# M3_Chip.net
KiCad netlist of a schematic drawn in Altium Designer
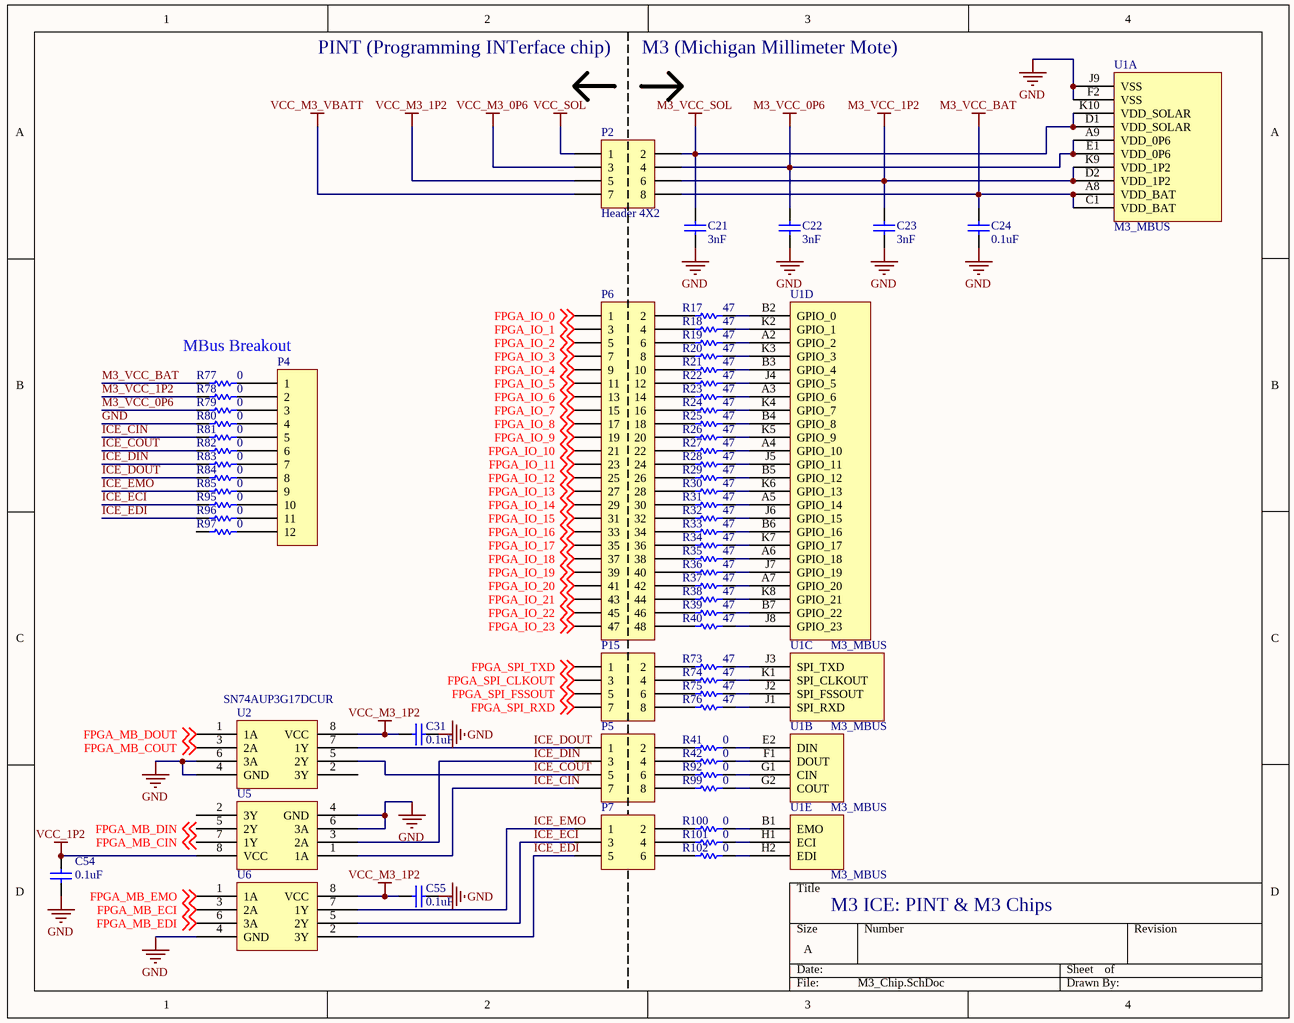
[diagram p0: M3_Chip.SchDoc]

(export (version "E")
  (design (tool "Eeschema 10.0.6"))
  (components
    (comp (ref "C21")
      (value "3nF")
      (footprint "1608[0603]")
      (description "Capacitor (Semiconductor SIM Model)")
      (fields
        (field (name "DISTPARTNO") "399-7893-1-ND")
        (field (name "MANPARTNO") "C0603C302K5GACTU")
        (field (name "PUBLISHER") "Altium Limited")
      )
      (libsource (lib "Miscellaneous Devices") (part "Cap Semi"))
    )
    (comp (ref "C22")
      (value "3nF")
      (footprint "1608[0603]")
      (description "Capacitor (Semiconductor SIM Model)")
      (fields
        (field (name "DISTPARTNO") "399-7893-1-ND")
        (field (name "MANPARTNO") "C0603C302K5GACTU")
        (field (name "PUBLISHER") "Altium Limited")
      )
      (libsource (lib "Miscellaneous Devices") (part "Cap Semi"))
    )
    (comp (ref "C23")
      (value "3nF")
      (footprint "1608[0603]")
      (description "Capacitor (Semiconductor SIM Model)")
      (fields
        (field (name "DISTPARTNO") "399-7893-1-ND")
        (field (name "MANPARTNO") "C0603C302K5GACTU")
        (field (name "PUBLISHER") "Altium Limited")
      )
      (libsource (lib "Miscellaneous Devices") (part "Cap Semi"))
    )
    (comp (ref "C24")
      (value "0.1uF")
      (footprint "1608[0603]")
      (description "Capacitor (Semiconductor SIM Model)")
      (fields
        (field (name "DISTPARTNO") "445-1317-1-ND")
        (field (name "MANPARTNO") "C1608X7R1C104K")
        (field (name "PUBLISHER") "Altium Limited")
      )
      (libsource (lib "Miscellaneous Devices") (part "Cap Semi"))
    )
    (comp (ref "C31")
      (value "0.1uF")
      (footprint "1608[0603]")
      (description "Capacitor (Semiconductor SIM Model)")
      (fields
        (field (name "DISTPARTNO") "445-1317-1-ND")
        (field (name "MANPARTNO") "C1608X7R1C104K")
        (field (name "PUBLISHER") "Altium Limited")
      )
      (libsource (lib "Miscellaneous Devices") (part "Cap Semi"))
    )
    (comp (ref "C54")
      (value "0.1uF")
      (footprint "1608[0603]")
      (description "Capacitor (Semiconductor SIM Model)")
      (fields
        (field (name "DISTPARTNO") "445-1317-1-ND")
        (field (name "MANPARTNO") "C1608X7R1C104K")
        (field (name "PUBLISHER") "Altium Limited")
      )
      (libsource (lib "Miscellaneous Devices") (part "Cap Semi"))
    )
    (comp (ref "C55")
      (value "0.1uF")
      (footprint "1608[0603]")
      (description "Capacitor (Semiconductor SIM Model)")
      (fields
        (field (name "DISTPARTNO") "445-1317-1-ND")
        (field (name "MANPARTNO") "C1608X7R1C104K")
        (field (name "PUBLISHER") "Altium Limited")
      )
      (libsource (lib "Miscellaneous Devices") (part "Cap Semi"))
    )
    (comp (ref "P2")
      (value "Header 4X2")
      (footprint "HDR2X4")
      (description "Header, 4-Pin, Dual row")
      (fields (field (name "PUBLISHER") "Altium Limited"))
      (libsource (lib "Miscellaneous Connectors") (part "Header 4X2"))
    )
    (comp (ref "P4")
      (value "MBus Breakout")
      (footprint "HDR1X12")
      (description "Header, 12-Pin")
      (fields (field (name "PUBLISHER") "Altium Limited"))
      (libsource (lib "Miscellaneous Connectors") (part "Header 12"))
    )
    (comp (ref "P5")
      (value "Header 4X2")
      (footprint "HDR2X4")
      (description "Header, 4-Pin, Dual row")
      (fields (field (name "PUBLISHER") "Altium Limited"))
      (libsource (lib "Miscellaneous Connectors") (part "Header 4X2"))
    )
    (comp (ref "P6")
      (value "Header 24X2")
      (footprint "HDR2X24")
      (description "Header, 24-Pin, Dual row")
      (fields (field (name "MANPARTNO") "4-103328-0") (field (name "PUBLISHER") "Altium Limited"))
      (libsource (lib "Miscellaneous Connectors") (part "Header 24X2"))
    )
    (comp (ref "P7")
      (value "Header 3X2")
      (footprint "HDR2X3")
      (description "Header, 3-Pin, Dual row")
      (fields (field (name "PUBLISHER") "Altium Limited"))
      (libsource (lib "Miscellaneous Connectors") (part "Header 3X2"))
    )
    (comp (ref "P15")
      (value "Header 4X2")
      (footprint "HDR2X4")
      (description "Header, 4-Pin, Dual row")
      (fields (field (name "PUBLISHER") "Altium Limited"))
      (libsource (lib "Miscellaneous Connectors") (part "Header 4X2"))
    )
    (comp (ref "R17")
      (value "47")
      (footprint "0603")
      (description "Semiconductor Resistor")
      (fields
        (field (name "DISTPARTNO") "P47GCT-ND")
        (field (name "MANPARTNO") "ERJ-3GEYJ470V")
        (field (name "PUBLISHER") "Altium Limited")
      )
      (libsource (lib "M3") (part "Res Chip"))
    )
    (comp (ref "R18")
      (value "47")
      (footprint "0603")
      (description "Semiconductor Resistor")
      (fields
        (field (name "DISTPARTNO") "P47GCT-ND")
        (field (name "MANPARTNO") "ERJ-3GEYJ470V")
        (field (name "PUBLISHER") "Altium Limited")
      )
      (libsource (lib "M3") (part "Res Chip"))
    )
    (comp (ref "R19")
      (value "47")
      (footprint "0603")
      (description "Semiconductor Resistor")
      (fields
        (field (name "DISTPARTNO") "P47GCT-ND")
        (field (name "MANPARTNO") "ERJ-3GEYJ470V")
        (field (name "PUBLISHER") "Altium Limited")
      )
      (libsource (lib "M3") (part "Res Chip"))
    )
    (comp (ref "R20")
      (value "47")
      (footprint "0603")
      (description "Semiconductor Resistor")
      (fields
        (field (name "DISTPARTNO") "P47GCT-ND")
        (field (name "MANPARTNO") "ERJ-3GEYJ470V")
        (field (name "PUBLISHER") "Altium Limited")
      )
      (libsource (lib "M3") (part "Res Chip"))
    )
    (comp (ref "R21")
      (value "47")
      (footprint "0603")
      (description "Semiconductor Resistor")
      (fields
        (field (name "DISTPARTNO") "P47GCT-ND")
        (field (name "MANPARTNO") "ERJ-3GEYJ470V")
        (field (name "PUBLISHER") "Altium Limited")
      )
      (libsource (lib "M3") (part "Res Chip"))
    )
    (comp (ref "R22")
      (value "47")
      (footprint "0603")
      (description "Semiconductor Resistor")
      (fields
        (field (name "DISTPARTNO") "P47GCT-ND")
        (field (name "MANPARTNO") "ERJ-3GEYJ470V")
        (field (name "PUBLISHER") "Altium Limited")
      )
      (libsource (lib "M3") (part "Res Chip"))
    )
    (comp (ref "R23")
      (value "47")
      (footprint "0603")
      (description "Semiconductor Resistor")
      (fields
        (field (name "DISTPARTNO") "P47GCT-ND")
        (field (name "MANPARTNO") "ERJ-3GEYJ470V")
        (field (name "PUBLISHER") "Altium Limited")
      )
      (libsource (lib "M3") (part "Res Chip"))
    )
    (comp (ref "R24")
      (value "47")
      (footprint "0603")
      (description "Semiconductor Resistor")
      (fields
        (field (name "DISTPARTNO") "P47GCT-ND")
        (field (name "MANPARTNO") "ERJ-3GEYJ470V")
        (field (name "PUBLISHER") "Altium Limited")
      )
      (libsource (lib "M3") (part "Res Chip"))
    )
    (comp (ref "R25")
      (value "47")
      (footprint "0603")
      (description "Semiconductor Resistor")
      (fields
        (field (name "DISTPARTNO") "P47GCT-ND")
        (field (name "MANPARTNO") "ERJ-3GEYJ470V")
        (field (name "PUBLISHER") "Altium Limited")
      )
      (libsource (lib "M3") (part "Res Chip"))
    )
    (comp (ref "R26")
      (value "47")
      (footprint "0603")
      (description "Semiconductor Resistor")
      (fields
        (field (name "DISTPARTNO") "P47GCT-ND")
        (field (name "MANPARTNO") "ERJ-3GEYJ470V")
        (field (name "PUBLISHER") "Altium Limited")
      )
      (libsource (lib "M3") (part "Res Chip"))
    )
    (comp (ref "R27")
      (value "47")
      (footprint "0603")
      (description "Semiconductor Resistor")
      (fields
        (field (name "DISTPARTNO") "P47GCT-ND")
        (field (name "MANPARTNO") "ERJ-3GEYJ470V")
        (field (name "PUBLISHER") "Altium Limited")
      )
      (libsource (lib "M3") (part "Res Chip"))
    )
    (comp (ref "R28")
      (value "47")
      (footprint "0603")
      (description "Semiconductor Resistor")
      (fields
        (field (name "DISTPARTNO") "P47GCT-ND")
        (field (name "MANPARTNO") "ERJ-3GEYJ470V")
        (field (name "PUBLISHER") "Altium Limited")
      )
      (libsource (lib "M3") (part "Res Chip"))
    )
    (comp (ref "R29")
      (value "47")
      (footprint "0603")
      (description "Semiconductor Resistor")
      (fields
        (field (name "DISTPARTNO") "P47GCT-ND")
        (field (name "MANPARTNO") "ERJ-3GEYJ470V")
        (field (name "PUBLISHER") "Altium Limited")
      )
      (libsource (lib "M3") (part "Res Chip"))
    )
    (comp (ref "R30")
      (value "47")
      (footprint "0603")
      (description "Semiconductor Resistor")
      (fields
        (field (name "DISTPARTNO") "P47GCT-ND")
        (field (name "MANPARTNO") "ERJ-3GEYJ470V")
        (field (name "PUBLISHER") "Altium Limited")
      )
      (libsource (lib "M3") (part "Res Chip"))
    )
    (comp (ref "R31")
      (value "47")
      (footprint "0603")
      (description "Semiconductor Resistor")
      (fields
        (field (name "DISTPARTNO") "P47GCT-ND")
        (field (name "MANPARTNO") "ERJ-3GEYJ470V")
        (field (name "PUBLISHER") "Altium Limited")
      )
      (libsource (lib "M3") (part "Res Chip"))
    )
    (comp (ref "R32")
      (value "47")
      (footprint "0603")
      (description "Semiconductor Resistor")
      (fields
        (field (name "DISTPARTNO") "P47GCT-ND")
        (field (name "MANPARTNO") "ERJ-3GEYJ470V")
        (field (name "PUBLISHER") "Altium Limited")
      )
      (libsource (lib "M3") (part "Res Chip"))
    )
    (comp (ref "R33")
      (value "47")
      (footprint "0603")
      (description "Semiconductor Resistor")
      (fields
        (field (name "DISTPARTNO") "P47GCT-ND")
        (field (name "MANPARTNO") "ERJ-3GEYJ470V")
        (field (name "PUBLISHER") "Altium Limited")
      )
      (libsource (lib "M3") (part "Res Chip"))
    )
    (comp (ref "R34")
      (value "47")
      (footprint "0603")
      (description "Semiconductor Resistor")
      (fields
        (field (name "DISTPARTNO") "P47GCT-ND")
        (field (name "MANPARTNO") "ERJ-3GEYJ470V")
        (field (name "PUBLISHER") "Altium Limited")
      )
      (libsource (lib "M3") (part "Res Chip"))
    )
    (comp (ref "R35")
      (value "47")
      (footprint "0603")
      (description "Semiconductor Resistor")
      (fields
        (field (name "DISTPARTNO") "P47GCT-ND")
        (field (name "MANPARTNO") "ERJ-3GEYJ470V")
        (field (name "PUBLISHER") "Altium Limited")
      )
      (libsource (lib "M3") (part "Res Chip"))
    )
    (comp (ref "R36")
      (value "47")
      (footprint "0603")
      (description "Semiconductor Resistor")
      (fields
        (field (name "DISTPARTNO") "P47GCT-ND")
        (field (name "MANPARTNO") "ERJ-3GEYJ470V")
        (field (name "PUBLISHER") "Altium Limited")
      )
      (libsource (lib "M3") (part "Res Chip"))
    )
    (comp (ref "R37")
      (value "47")
      (footprint "0603")
      (description "Semiconductor Resistor")
      (fields
        (field (name "DISTPARTNO") "P47GCT-ND")
        (field (name "MANPARTNO") "ERJ-3GEYJ470V")
        (field (name "PUBLISHER") "Altium Limited")
      )
      (libsource (lib "M3") (part "Res Chip"))
    )
    (comp (ref "R38")
      (value "47")
      (footprint "0603")
      (description "Semiconductor Resistor")
      (fields
        (field (name "DISTPARTNO") "P47GCT-ND")
        (field (name "MANPARTNO") "ERJ-3GEYJ470V")
        (field (name "PUBLISHER") "Altium Limited")
      )
      (libsource (lib "M3") (part "Res Chip"))
    )
    (comp (ref "R39")
      (value "47")
      (footprint "0603")
      (description "Semiconductor Resistor")
      (fields
        (field (name "DISTPARTNO") "P47GCT-ND")
        (field (name "MANPARTNO") "ERJ-3GEYJ470V")
        (field (name "PUBLISHER") "Altium Limited")
      )
      (libsource (lib "M3") (part "Res Chip"))
    )
    (comp (ref "R40")
      (value "47")
      (footprint "0603")
      (description "Semiconductor Resistor")
      (fields
        (field (name "DISTPARTNO") "P47GCT-ND")
        (field (name "MANPARTNO") "ERJ-3GEYJ470V")
        (field (name "PUBLISHER") "Altium Limited")
      )
      (libsource (lib "M3") (part "Res Chip"))
    )
    (comp (ref "R41")
      (value "0")
      (footprint "0603")
      (description "Semiconductor Resistor")
      (fields
        (field (name "DISTPARTNO") "P0.0GCT-ND")
        (field (name "MANPARTNO") "ERJ-3GEY0R00V")
        (field (name "PUBLISHER") "Altium Limited")
      )
      (libsource (lib "M3") (part "Res Chip"))
    )
    (comp (ref "R42")
      (value "0")
      (footprint "0603")
      (description "Semiconductor Resistor")
      (fields
        (field (name "DISTPARTNO") "P0.0GCT-ND")
        (field (name "MANPARTNO") "ERJ-3GEY0R00V")
        (field (name "PUBLISHER") "Altium Limited")
      )
      (libsource (lib "M3") (part "Res Chip"))
    )
    (comp (ref "R73")
      (value "47")
      (footprint "0603")
      (description "Semiconductor Resistor")
      (fields
        (field (name "DISTPARTNO") "P47GCT-ND")
        (field (name "MANPARTNO") "ERJ-3GEYJ470V")
        (field (name "PUBLISHER") "Altium Limited")
      )
      (libsource (lib "M3") (part "Res Chip"))
    )
    (comp (ref "R74")
      (value "47")
      (footprint "0603")
      (description "Semiconductor Resistor")
      (fields
        (field (name "DISTPARTNO") "P47GCT-ND")
        (field (name "MANPARTNO") "ERJ-3GEYJ470V")
        (field (name "PUBLISHER") "Altium Limited")
      )
      (libsource (lib "M3") (part "Res Chip"))
    )
    (comp (ref "R75")
      (value "47")
      (footprint "0603")
      (description "Semiconductor Resistor")
      (fields
        (field (name "DISTPARTNO") "P47GCT-ND")
        (field (name "MANPARTNO") "ERJ-3GEYJ470V")
        (field (name "PUBLISHER") "Altium Limited")
      )
      (libsource (lib "M3") (part "Res Chip"))
    )
    (comp (ref "R76")
      (value "47")
      (footprint "0603")
      (description "Semiconductor Resistor")
      (fields
        (field (name "DISTPARTNO") "P47GCT-ND")
        (field (name "MANPARTNO") "ERJ-3GEYJ470V")
        (field (name "PUBLISHER") "Altium Limited")
      )
      (libsource (lib "M3") (part "Res Chip"))
    )
    (comp (ref "R77")
      (value "0")
      (footprint "0603")
      (description "Semiconductor Resistor")
      (fields
        (field (name "DISTPARTNO") "P0.0GCT-ND")
        (field (name "MANPARTNO") "ERJ-3GEY0R00V")
        (field (name "PUBLISHER") "Altium Limited")
      )
      (libsource (lib "M3") (part "Res Chip"))
    )
    (comp (ref "R78")
      (value "0")
      (footprint "0603")
      (description "Semiconductor Resistor")
      (fields
        (field (name "DISTPARTNO") "P0.0GCT-ND")
        (field (name "MANPARTNO") "ERJ-3GEY0R00V")
        (field (name "PUBLISHER") "Altium Limited")
      )
      (libsource (lib "M3") (part "Res Chip"))
    )
    (comp (ref "R79")
      (value "0")
      (footprint "0603")
      (description "Semiconductor Resistor")
      (fields
        (field (name "DISTPARTNO") "P0.0GCT-ND")
        (field (name "MANPARTNO") "ERJ-3GEY0R00V")
        (field (name "PUBLISHER") "Altium Limited")
      )
      (libsource (lib "M3") (part "Res Chip"))
    )
    (comp (ref "R80")
      (value "0")
      (footprint "0603")
      (description "Semiconductor Resistor")
      (fields
        (field (name "DISTPARTNO") "P0.0GCT-ND")
        (field (name "MANPARTNO") "ERJ-3GEY0R00V")
        (field (name "PUBLISHER") "Altium Limited")
      )
      (libsource (lib "M3") (part "Res Chip"))
    )
    (comp (ref "R81")
      (value "0")
      (footprint "0603")
      (description "Semiconductor Resistor")
      (fields
        (field (name "DISTPARTNO") "P0.0GCT-ND")
        (field (name "MANPARTNO") "ERJ-3GEY0R00V")
        (field (name "PUBLISHER") "Altium Limited")
      )
      (libsource (lib "M3") (part "Res Chip"))
    )
    (comp (ref "R82")
      (value "0")
      (footprint "0603")
      (description "Semiconductor Resistor")
      (fields
        (field (name "DISTPARTNO") "P0.0GCT-ND")
        (field (name "MANPARTNO") "ERJ-3GEY0R00V")
        (field (name "PUBLISHER") "Altium Limited")
      )
      (libsource (lib "M3") (part "Res Chip"))
    )
    (comp (ref "R83")
      (value "0")
      (footprint "0603")
      (description "Semiconductor Resistor")
      (fields
        (field (name "DISTPARTNO") "P0.0GCT-ND")
        (field (name "MANPARTNO") "ERJ-3GEY0R00V")
        (field (name "PUBLISHER") "Altium Limited")
      )
      (libsource (lib "M3") (part "Res Chip"))
    )
    (comp (ref "R84")
      (value "0")
      (footprint "0603")
      (description "Semiconductor Resistor")
      (fields
        (field (name "DISTPARTNO") "P0.0GCT-ND")
        (field (name "MANPARTNO") "ERJ-3GEY0R00V")
        (field (name "PUBLISHER") "Altium Limited")
      )
      (libsource (lib "M3") (part "Res Chip"))
    )
    (comp (ref "R85")
      (value "0")
      (footprint "0603")
      (description "Semiconductor Resistor")
      (fields
        (field (name "DISTPARTNO") "P0.0GCT-ND")
        (field (name "MANPARTNO") "ERJ-3GEY0R00V")
        (field (name "PUBLISHER") "Altium Limited")
      )
      (libsource (lib "M3") (part "Res Chip"))
    )
    (comp (ref "R92")
      (value "0")
      (footprint "0603")
      (description "Semiconductor Resistor")
      (fields
        (field (name "DISTPARTNO") "P0.0GCT-ND")
        (field (name "MANPARTNO") "ERJ-3GEY0R00V")
        (field (name "PUBLISHER") "Altium Limited")
      )
      (libsource (lib "M3") (part "Res Chip"))
    )
    (comp (ref "R95")
      (value "0")
      (footprint "0603")
      (description "Semiconductor Resistor")
      (fields
        (field (name "DISTPARTNO") "P0.0GCT-ND")
        (field (name "MANPARTNO") "ERJ-3GEY0R00V")
        (field (name "PUBLISHER") "Altium Limited")
      )
      (libsource (lib "M3") (part "Res Chip"))
    )
    (comp (ref "R96")
      (value "0")
      (footprint "0603")
      (description "Semiconductor Resistor")
      (fields
        (field (name "DISTPARTNO") "P0.0GCT-ND")
        (field (name "MANPARTNO") "ERJ-3GEY0R00V")
        (field (name "PUBLISHER") "Altium Limited")
      )
      (libsource (lib "M3") (part "Res Chip"))
    )
    (comp (ref "R97")
      (value "0")
      (footprint "0603")
      (description "Semiconductor Resistor")
      (fields
        (field (name "DISTPARTNO") "P0.0GCT-ND")
        (field (name "MANPARTNO") "ERJ-3GEY0R00V")
        (field (name "PUBLISHER") "Altium Limited")
      )
      (libsource (lib "M3") (part "Res Chip"))
    )
    (comp (ref "R99")
      (value "0")
      (footprint "0603")
      (description "Semiconductor Resistor")
      (fields
        (field (name "DISTPARTNO") "P0.0GCT-ND")
        (field (name "MANPARTNO") "ERJ-3GEY0R00V")
        (field (name "PUBLISHER") "Altium Limited")
      )
      (libsource (lib "M3") (part "Res Chip"))
    )
    (comp (ref "R100")
      (value "0")
      (footprint "0603")
      (description "Semiconductor Resistor")
      (fields
        (field (name "DISTPARTNO") "P0.0GCT-ND")
        (field (name "MANPARTNO") "ERJ-3GEY0R00V")
        (field (name "PUBLISHER") "Altium Limited")
      )
      (libsource (lib "M3") (part "Res Chip"))
    )
    (comp (ref "R101")
      (value "0")
      (footprint "0603")
      (description "Semiconductor Resistor")
      (fields
        (field (name "DISTPARTNO") "P0.0GCT-ND")
        (field (name "MANPARTNO") "ERJ-3GEY0R00V")
        (field (name "PUBLISHER") "Altium Limited")
      )
      (libsource (lib "M3") (part "Res Chip"))
    )
    (comp (ref "R102")
      (value "0")
      (footprint "0603")
      (description "Semiconductor Resistor")
      (fields
        (field (name "DISTPARTNO") "P0.0GCT-ND")
        (field (name "MANPARTNO") "ERJ-3GEY0R00V")
        (field (name "PUBLISHER") "Altium Limited")
      )
      (libsource (lib "M3") (part "Res Chip"))
    )
    (comp (ref "U1")
      (value "M3_MBUS")
      (footprint "CPGA-65")
      (fields (field (name "DISTPARTNO") "3M5067-ND") (field (name "MANPARTNO") "200-6311-9UN-1900"))
      (libsource (lib "M3") (part "M3_MBUS"))
    )
    (comp (ref "U2")
      (value "SN74AUP3G17DCUR")
      (footprint "VFSOP-8")
      (fields (field (name "DISTPARTNO") "296-25596-1-ND"))
      (libsource (lib "") (part "SN74AUP3G17DCUR_1"))
    )
    (comp (ref "U5")
      (value "SN74AUP3G17DCUR")
      (footprint "VFSOP-8")
      (fields (field (name "DISTPARTNO") "296-25596-1-ND"))
      (libsource (lib "M3") (part "SN74AUP3G17DCUR"))
    )
    (comp (ref "U6")
      (value "SN74AUP3G17DCUR")
      (footprint "VFSOP-8")
      (fields (field (name "DISTPARTNO") "296-25596-1-ND"))
      (libsource (lib "") (part "SN74AUP3G17DCUR_1"))
    )
  )
  (nets
    (net (code "1") (name "/ICE_CIN") (class "Default")
      (node (ref "P5") (pin "7") (pinfunction "7_7") (pintype "passive"))
      (node (ref "R81") (pin "2") (pinfunction "2_2") (pintype "passive"))
      (node (ref "U5") (pin "1") (pinfunction "1A_1") (pintype "passive"))
    )
    (net (code "2") (name "/ICE_COUT") (class "Default")
      (node (ref "P5") (pin "5") (pinfunction "5_5") (pintype "passive"))
      (node (ref "R82") (pin "2") (pinfunction "2_2") (pintype "passive"))
      (node (ref "U2") (pin "5") (pinfunction "2Y_5") (pintype "passive"))
    )
    (net (code "3") (name "/ICE_DIN") (class "Default")
      (node (ref "P5") (pin "3") (pinfunction "3_3") (pintype "passive"))
      (node (ref "R83") (pin "2") (pinfunction "2_2") (pintype "passive"))
      (node (ref "U5") (pin "3") (pinfunction "2A_3") (pintype "passive"))
    )
    (net (code "4") (name "/ICE_DOUT") (class "Default")
      (node (ref "P5") (pin "1") (pinfunction "1_1") (pintype "passive"))
      (node (ref "R84") (pin "2") (pinfunction "2_2") (pintype "passive"))
      (node (ref "U2") (pin "7") (pinfunction "1Y_7") (pintype "passive"))
    )
    (net (code "5") (name "/ICE_ECI") (class "Default")
      (node (ref "P7") (pin "3") (pinfunction "3_3") (pintype "passive"))
      (node (ref "R95") (pin "2") (pinfunction "2_2") (pintype "passive"))
      (node (ref "U6") (pin "5") (pinfunction "2Y_5") (pintype "passive"))
    )
    (net (code "6") (name "/ICE_EDI") (class "Default")
      (node (ref "P7") (pin "5") (pinfunction "5_5") (pintype "passive"))
      (node (ref "R96") (pin "2") (pinfunction "2_2") (pintype "passive"))
      (node (ref "U6") (pin "2") (pinfunction "3Y_2") (pintype "passive"))
    )
    (net (code "7") (name "/ICE_EMO") (class "Default")
      (node (ref "P7") (pin "1") (pinfunction "1_1") (pintype "passive"))
      (node (ref "R85") (pin "2") (pinfunction "2_2") (pintype "passive"))
      (node (ref "U6") (pin "7") (pinfunction "1Y_7") (pintype "passive"))
    )
    (net (code "8") (name "FPGA_IO_0") (class "Default")
      (node (ref "P6") (pin "1") (pinfunction "1_1") (pintype "passive"))
    )
    (net (code "9") (name "FPGA_IO_1") (class "Default")
      (node (ref "P6") (pin "3") (pinfunction "3_3") (pintype "passive"))
    )
    (net (code "10") (name "FPGA_IO_2") (class "Default")
      (node (ref "P6") (pin "5") (pinfunction "5_5") (pintype "passive"))
    )
    (net (code "11") (name "FPGA_IO_3") (class "Default")
      (node (ref "P6") (pin "7") (pinfunction "7_7") (pintype "passive"))
    )
    (net (code "12") (name "FPGA_IO_4") (class "Default")
      (node (ref "P6") (pin "9") (pinfunction "9_9") (pintype "passive"))
    )
    (net (code "13") (name "FPGA_IO_5") (class "Default")
      (node (ref "P6") (pin "11") (pinfunction "11_11") (pintype "passive"))
    )
    (net (code "14") (name "FPGA_IO_6") (class "Default")
      (node (ref "P6") (pin "13") (pinfunction "13_13") (pintype "passive"))
    )
    (net (code "15") (name "FPGA_IO_7") (class "Default")
      (node (ref "P6") (pin "15") (pinfunction "15_15") (pintype "passive"))
    )
    (net (code "16") (name "FPGA_IO_8") (class "Default")
      (node (ref "P6") (pin "17") (pinfunction "17_17") (pintype "passive"))
    )
    (net (code "17") (name "FPGA_IO_9") (class "Default")
      (node (ref "P6") (pin "19") (pinfunction "19_19") (pintype "passive"))
    )
    (net (code "18") (name "FPGA_IO_10") (class "Default")
      (node (ref "P6") (pin "21") (pinfunction "21_21") (pintype "passive"))
    )
    (net (code "19") (name "FPGA_IO_11") (class "Default")
      (node (ref "P6") (pin "23") (pinfunction "23_23") (pintype "passive"))
    )
    (net (code "20") (name "FPGA_IO_12") (class "Default")
      (node (ref "P6") (pin "25") (pinfunction "25_25") (pintype "passive"))
    )
    (net (code "21") (name "FPGA_IO_13") (class "Default")
      (node (ref "P6") (pin "27") (pinfunction "27_27") (pintype "passive"))
    )
    (net (code "22") (name "FPGA_IO_14") (class "Default")
      (node (ref "P6") (pin "29") (pinfunction "29_29") (pintype "passive"))
    )
    (net (code "23") (name "FPGA_IO_15") (class "Default")
      (node (ref "P6") (pin "31") (pinfunction "31_31") (pintype "passive"))
    )
    (net (code "24") (name "FPGA_IO_16") (class "Default")
      (node (ref "P6") (pin "33") (pinfunction "33_33") (pintype "passive"))
    )
    (net (code "25") (name "FPGA_IO_17") (class "Default")
      (node (ref "P6") (pin "35") (pinfunction "35_35") (pintype "passive"))
    )
    (net (code "26") (name "FPGA_IO_18") (class "Default")
      (node (ref "P6") (pin "37") (pinfunction "37_37") (pintype "passive"))
    )
    (net (code "27") (name "FPGA_IO_19") (class "Default")
      (node (ref "P6") (pin "39") (pinfunction "39_39") (pintype "passive"))
    )
    (net (code "28") (name "FPGA_IO_20") (class "Default")
      (node (ref "P6") (pin "41") (pinfunction "41_41") (pintype "passive"))
    )
    (net (code "29") (name "FPGA_IO_21") (class "Default")
      (node (ref "P6") (pin "43") (pinfunction "43_43") (pintype "passive"))
    )
    (net (code "30") (name "FPGA_IO_22") (class "Default")
      (node (ref "P6") (pin "45") (pinfunction "45_45") (pintype "passive"))
    )
    (net (code "31") (name "FPGA_IO_23") (class "Default")
      (node (ref "P6") (pin "47") (pinfunction "47_47") (pintype "passive"))
    )
    (net (code "32") (name "FPGA_MB_CIN") (class "Default")
      (node (ref "U5") (pin "7") (pinfunction "1Y_7") (pintype "passive"))
    )
    (net (code "33") (name "FPGA_MB_COUT") (class "Default")
      (node (ref "U2") (pin "3") (pinfunction "2A_3") (pintype "passive"))
    )
    (net (code "34") (name "FPGA_MB_DIN") (class "Default")
      (node (ref "U5") (pin "5") (pinfunction "2Y_5") (pintype "passive"))
    )
    (net (code "35") (name "FPGA_MB_DOUT") (class "Default")
      (node (ref "U2") (pin "1") (pinfunction "1A_1") (pintype "passive"))
    )
    (net (code "36") (name "FPGA_MB_ECI") (class "Default")
      (node (ref "U6") (pin "3") (pinfunction "2A_3") (pintype "passive"))
    )
    (net (code "37") (name "FPGA_MB_EDI") (class "Default")
      (node (ref "U6") (pin "6") (pinfunction "3A_6") (pintype "passive"))
    )
    (net (code "38") (name "FPGA_MB_EMO") (class "Default")
      (node (ref "U6") (pin "1") (pinfunction "1A_1") (pintype "passive"))
    )
    (net (code "39") (name "FPGA_SPI_CLKOUT") (class "Default")
      (node (ref "P15") (pin "3") (pinfunction "3_3") (pintype "passive"))
    )
    (net (code "40") (name "FPGA_SPI_FSSOUT") (class "Default")
      (node (ref "P15") (pin "5") (pinfunction "5_5") (pintype "passive"))
    )
    (net (code "41") (name "FPGA_SPI_RXD") (class "Default")
      (node (ref "P15") (pin "7") (pinfunction "7_7") (pintype "passive"))
    )
    (net (code "42") (name "FPGA_SPI_TXD") (class "Default")
      (node (ref "P15") (pin "1") (pinfunction "1_1") (pintype "passive"))
    )
    (net (code "43") (name "GND") (class "Default")
      (node (ref "C21") (pin "1") (pinfunction "1_1") (pintype "passive"))
      (node (ref "C22") (pin "1") (pinfunction "1_1") (pintype "passive"))
      (node (ref "C23") (pin "1") (pinfunction "1_1") (pintype "passive"))
      (node (ref "C24") (pin "1") (pinfunction "1_1") (pintype "passive"))
      (node (ref "C31") (pin "1") (pinfunction "1_1") (pintype "passive"))
      (node (ref "C54") (pin "1") (pinfunction "1_1") (pintype "passive"))
      (node (ref "C55") (pin "1") (pinfunction "1_1") (pintype "passive"))
      (node (ref "R80") (pin "2") (pinfunction "2_2") (pintype "passive"))
      (node (ref "U1") (pin "F2") (pinfunction "VSS_F2") (pintype "passive"))
      (node (ref "U1") (pin "J9") (pinfunction "VSS_J9") (pintype "passive"))
      (node (ref "U2") (pin "4") (pinfunction "GND_4") (pintype "passive"))
      (node (ref "U2") (pin "6") (pinfunction "3A_6") (pintype "passive"))
      (node (ref "U5") (pin "4") (pinfunction "GND_4") (pintype "passive"))
      (node (ref "U5") (pin "6") (pinfunction "3A_6") (pintype "passive"))
      (node (ref "U6") (pin "4") (pinfunction "GND_4") (pintype "passive"))
    )
    (net (code "44") (name "M3_VCC_0P6") (class "Default")
      (node (ref "C22") (pin "2") (pinfunction "2_2") (pintype "passive"))
      (node (ref "P2") (pin "4") (pinfunction "4_4") (pintype "passive"))
      (node (ref "R79") (pin "2") (pinfunction "2_2") (pintype "passive"))
      (node (ref "U1") (pin "A9") (pinfunction "VDD_0P6_A9") (pintype "passive"))
      (node (ref "U1") (pin "E1") (pinfunction "VDD_0P6_E1") (pintype "passive"))
    )
    (net (code "45") (name "M3_VCC_1P2") (class "Default")
      (node (ref "C23") (pin "2") (pinfunction "2_2") (pintype "passive"))
      (node (ref "P2") (pin "6") (pinfunction "6_6") (pintype "passive"))
      (node (ref "R78") (pin "2") (pinfunction "2_2") (pintype "passive"))
      (node (ref "U1") (pin "D2") (pinfunction "VDD_1P2_D2") (pintype "passive"))
      (node (ref "U1") (pin "K9") (pinfunction "VDD_1P2_K9") (pintype "passive"))
    )
    (net (code "46") (name "M3_VCC_BAT") (class "Default")
      (node (ref "C24") (pin "2") (pinfunction "2_2") (pintype "passive"))
      (node (ref "P2") (pin "8") (pinfunction "8_8") (pintype "passive"))
      (node (ref "R77") (pin "2") (pinfunction "2_2") (pintype "passive"))
      (node (ref "U1") (pin "A8") (pinfunction "VDD_BAT_A8") (pintype "passive"))
      (node (ref "U1") (pin "C1") (pinfunction "VDD_BAT_C1") (pintype "passive"))
    )
    (net (code "47") (name "M3_VCC_SOL") (class "Default")
      (node (ref "C21") (pin "2") (pinfunction "2_2") (pintype "passive"))
      (node (ref "P2") (pin "2") (pinfunction "2_2") (pintype "passive"))
      (node (ref "U1") (pin "D1") (pinfunction "VDD_SOLAR_D1") (pintype "passive"))
      (node (ref "U1") (pin "K10") (pinfunction "VDD_SOLAR_K10") (pintype "passive"))
    )
    (net (code "48") (name "Net-(P4-Pad1)") (class "Default")
      (node (ref "P4") (pin "1") (pinfunction "1_1") (pintype "passive"))
      (node (ref "R77") (pin "1") (pinfunction "1_1") (pintype "passive"))
    )
    (net (code "49") (name "Net-(P4-Pad2)") (class "Default")
      (node (ref "P4") (pin "2") (pinfunction "2_2") (pintype "passive"))
      (node (ref "R78") (pin "1") (pinfunction "1_1") (pintype "passive"))
    )
    (net (code "50") (name "Net-(P4-Pad3)") (class "Default")
      (node (ref "P4") (pin "3") (pinfunction "3_3") (pintype "passive"))
      (node (ref "R79") (pin "1") (pinfunction "1_1") (pintype "passive"))
    )
    (net (code "51") (name "Net-(P4-Pad4)") (class "Default")
      (node (ref "P4") (pin "4") (pinfunction "4_4") (pintype "passive"))
      (node (ref "R80") (pin "1") (pinfunction "1_1") (pintype "passive"))
    )
    (net (code "52") (name "Net-(P4-Pad5)") (class "Default")
      (node (ref "P4") (pin "5") (pinfunction "5_5") (pintype "passive"))
      (node (ref "R81") (pin "1") (pinfunction "1_1") (pintype "passive"))
    )
    (net (code "53") (name "Net-(P4-Pad6)") (class "Default")
      (node (ref "P4") (pin "6") (pinfunction "6_6") (pintype "passive"))
      (node (ref "R82") (pin "1") (pinfunction "1_1") (pintype "passive"))
    )
    (net (code "54") (name "Net-(P4-Pad7)") (class "Default")
      (node (ref "P4") (pin "7") (pinfunction "7_7") (pintype "passive"))
      (node (ref "R83") (pin "1") (pinfunction "1_1") (pintype "passive"))
    )
    (net (code "55") (name "Net-(P4-Pad8)") (class "Default")
      (node (ref "P4") (pin "8") (pinfunction "8_8") (pintype "passive"))
      (node (ref "R84") (pin "1") (pinfunction "1_1") (pintype "passive"))
    )
    (net (code "56") (name "Net-(P4-Pad9)") (class "Default")
      (node (ref "P4") (pin "9") (pinfunction "9_9") (pintype "passive"))
      (node (ref "R85") (pin "1") (pinfunction "1_1") (pintype "passive"))
    )
    (net (code "57") (name "Net-(P4-Pad10)") (class "Default")
      (node (ref "P4") (pin "10") (pinfunction "10_10") (pintype "passive"))
      (node (ref "R95") (pin "1") (pinfunction "1_1") (pintype "passive"))
    )
    (net (code "58") (name "Net-(P4-Pad11)") (class "Default")
      (node (ref "P4") (pin "11") (pinfunction "11_11") (pintype "passive"))
      (node (ref "R96") (pin "1") (pinfunction "1_1") (pintype "passive"))
    )
    (net (code "59") (name "Net-(P4-Pad12)") (class "Default")
      (node (ref "P4") (pin "12") (pinfunction "12_12") (pintype "passive"))
      (node (ref "R97") (pin "1") (pinfunction "1_1") (pintype "passive"))
    )
    (net (code "60") (name "Net-(P5-Pad2)") (class "Default")
      (node (ref "P5") (pin "2") (pinfunction "2_2") (pintype "passive"))
      (node (ref "R41") (pin "2") (pinfunction "2_2") (pintype "passive"))
    )
    (net (code "61") (name "Net-(P5-Pad4)") (class "Default")
      (node (ref "P5") (pin "4") (pinfunction "4_4") (pintype "passive"))
      (node (ref "R42") (pin "2") (pinfunction "2_2") (pintype "passive"))
    )
    (net (code "62") (name "Net-(P5-Pad6)") (class "Default")
      (node (ref "P5") (pin "6") (pinfunction "6_6") (pintype "passive"))
      (node (ref "R92") (pin "2") (pinfunction "2_2") (pintype "passive"))
    )
    (net (code "63") (name "Net-(P5-Pad8)") (class "Default")
      (node (ref "P5") (pin "8") (pinfunction "8_8") (pintype "passive"))
      (node (ref "R99") (pin "2") (pinfunction "2_2") (pintype "passive"))
    )
    (net (code "64") (name "Net-(P6-Pad2)") (class "Default")
      (node (ref "P6") (pin "2") (pinfunction "2_2") (pintype "passive"))
      (node (ref "R17") (pin "2") (pinfunction "2_2") (pintype "passive"))
    )
    (net (code "65") (name "Net-(P6-Pad4)") (class "Default")
      (node (ref "P6") (pin "4") (pinfunction "4_4") (pintype "passive"))
      (node (ref "R18") (pin "2") (pinfunction "2_2") (pintype "passive"))
    )
    (net (code "66") (name "Net-(P6-Pad6)") (class "Default")
      (node (ref "P6") (pin "6") (pinfunction "6_6") (pintype "passive"))
      (node (ref "R19") (pin "2") (pinfunction "2_2") (pintype "passive"))
    )
    (net (code "67") (name "Net-(P6-Pad8)") (class "Default")
      (node (ref "P6") (pin "8") (pinfunction "8_8") (pintype "passive"))
      (node (ref "R20") (pin "2") (pinfunction "2_2") (pintype "passive"))
    )
    (net (code "68") (name "Net-(P6-Pad10)") (class "Default")
      (node (ref "P6") (pin "10") (pinfunction "10_10") (pintype "passive"))
      (node (ref "R21") (pin "2") (pinfunction "2_2") (pintype "passive"))
    )
    (net (code "69") (name "Net-(P6-Pad12)") (class "Default")
      (node (ref "P6") (pin "12") (pinfunction "12_12") (pintype "passive"))
      (node (ref "R22") (pin "2") (pinfunction "2_2") (pintype "passive"))
    )
    (net (code "70") (name "Net-(P6-Pad14)") (class "Default")
      (node (ref "P6") (pin "14") (pinfunction "14_14") (pintype "passive"))
      (node (ref "R23") (pin "2") (pinfunction "2_2") (pintype "passive"))
    )
    (net (code "71") (name "Net-(P6-Pad16)") (class "Default")
      (node (ref "P6") (pin "16") (pinfunction "16_16") (pintype "passive"))
      (node (ref "R24") (pin "2") (pinfunction "2_2") (pintype "passive"))
    )
    (net (code "72") (name "Net-(P6-Pad18)") (class "Default")
      (node (ref "P6") (pin "18") (pinfunction "18_18") (pintype "passive"))
      (node (ref "R25") (pin "2") (pinfunction "2_2") (pintype "passive"))
    )
    (net (code "73") (name "Net-(P6-Pad20)") (class "Default")
      (node (ref "P6") (pin "20") (pinfunction "20_20") (pintype "passive"))
      (node (ref "R26") (pin "2") (pinfunction "2_2") (pintype "passive"))
    )
    (net (code "74") (name "Net-(P6-Pad22)") (class "Default")
      (node (ref "P6") (pin "22") (pinfunction "22_22") (pintype "passive"))
      (node (ref "R27") (pin "2") (pinfunction "2_2") (pintype "passive"))
    )
    (net (code "75") (name "Net-(P6-Pad24)") (class "Default")
      (node (ref "P6") (pin "24") (pinfunction "24_24") (pintype "passive"))
      (node (ref "R28") (pin "2") (pinfunction "2_2") (pintype "passive"))
    )
    (net (code "76") (name "Net-(P6-Pad26)") (class "Default")
      (node (ref "P6") (pin "26") (pinfunction "26_26") (pintype "passive"))
      (node (ref "R29") (pin "2") (pinfunction "2_2") (pintype "passive"))
    )
    (net (code "77") (name "Net-(P6-Pad28)") (class "Default")
      (node (ref "P6") (pin "28") (pinfunction "28_28") (pintype "passive"))
      (node (ref "R30") (pin "2") (pinfunction "2_2") (pintype "passive"))
    )
    (net (code "78") (name "Net-(P6-Pad30)") (class "Default")
      (node (ref "P6") (pin "30") (pinfunction "30_30") (pintype "passive"))
      (node (ref "R31") (pin "2") (pinfunction "2_2") (pintype "passive"))
    )
    (net (code "79") (name "Net-(P6-Pad32)") (class "Default")
      (node (ref "P6") (pin "32") (pinfunction "32_32") (pintype "passive"))
      (node (ref "R32") (pin "2") (pinfunction "2_2") (pintype "passive"))
    )
    (net (code "80") (name "Net-(P6-Pad34)") (class "Default")
      (node (ref "P6") (pin "34") (pinfunction "34_34") (pintype "passive"))
      (node (ref "R33") (pin "2") (pinfunction "2_2") (pintype "passive"))
    )
    (net (code "81") (name "Net-(P6-Pad36)") (class "Default")
      (node (ref "P6") (pin "36") (pinfunction "36_36") (pintype "passive"))
      (node (ref "R34") (pin "2") (pinfunction "2_2") (pintype "passive"))
    )
    (net (code "82") (name "Net-(P6-Pad38)") (class "Default")
      (node (ref "P6") (pin "38") (pinfunction "38_38") (pintype "passive"))
      (node (ref "R35") (pin "2") (pinfunction "2_2") (pintype "passive"))
    )
    (net (code "83") (name "Net-(P6-Pad40)") (class "Default")
      (node (ref "P6") (pin "40") (pinfunction "40_40") (pintype "passive"))
      (node (ref "R36") (pin "2") (pinfunction "2_2") (pintype "passive"))
    )
    (net (code "84") (name "Net-(P6-Pad42)") (class "Default")
      (node (ref "P6") (pin "42") (pinfunction "42_42") (pintype "passive"))
      (node (ref "R37") (pin "2") (pinfunction "2_2") (pintype "passive"))
    )
    (net (code "85") (name "Net-(P6-Pad44)") (class "Default")
      (node (ref "P6") (pin "44") (pinfunction "44_44") (pintype "passive"))
      (node (ref "R38") (pin "2") (pinfunction "2_2") (pintype "passive"))
    )
    (net (code "86") (name "Net-(P6-Pad46)") (class "Default")
      (node (ref "P6") (pin "46") (pinfunction "46_46") (pintype "passive"))
      (node (ref "R39") (pin "2") (pinfunction "2_2") (pintype "passive"))
    )
    (net (code "87") (name "Net-(P6-Pad48)") (class "Default")
      (node (ref "P6") (pin "48") (pinfunction "48_48") (pintype "passive"))
      (node (ref "R40") (pin "2") (pinfunction "2_2") (pintype "passive"))
    )
    (net (code "88") (name "Net-(P7-Pad2)") (class "Default")
      (node (ref "P7") (pin "2") (pinfunction "2_2") (pintype "passive"))
      (node (ref "R100") (pin "2") (pinfunction "2_2") (pintype "passive"))
    )
    (net (code "89") (name "Net-(P7-Pad4)") (class "Default")
      (node (ref "P7") (pin "4") (pinfunction "4_4") (pintype "passive"))
      (node (ref "R101") (pin "2") (pinfunction "2_2") (pintype "passive"))
    )
    (net (code "90") (name "Net-(P7-Pad6)") (class "Default")
      (node (ref "P7") (pin "6") (pinfunction "6_6") (pintype "passive"))
      (node (ref "R102") (pin "2") (pinfunction "2_2") (pintype "passive"))
    )
    (net (code "91") (name "Net-(P15-Pad2)") (class "Default")
      (node (ref "P15") (pin "2") (pinfunction "2_2") (pintype "passive"))
      (node (ref "R73") (pin "2") (pinfunction "2_2") (pintype "passive"))
    )
    (net (code "92") (name "Net-(P15-Pad4)") (class "Default")
      (node (ref "P15") (pin "4") (pinfunction "4_4") (pintype "passive"))
      (node (ref "R74") (pin "2") (pinfunction "2_2") (pintype "passive"))
    )
    (net (code "93") (name "Net-(P15-Pad6)") (class "Default")
      (node (ref "P15") (pin "6") (pinfunction "6_6") (pintype "passive"))
      (node (ref "R75") (pin "2") (pinfunction "2_2") (pintype "passive"))
    )
    (net (code "94") (name "Net-(P15-Pad8)") (class "Default")
      (node (ref "P15") (pin "8") (pinfunction "8_8") (pintype "passive"))
      (node (ref "R76") (pin "2") (pinfunction "2_2") (pintype "passive"))
    )
    (net (code "95") (name "Net-(U1B-CIN)") (class "Default")
      (node (ref "R92") (pin "1") (pinfunction "1_1") (pintype "passive"))
      (node (ref "U1") (pin "G1") (pinfunction "CIN_G1") (pintype "passive"))
    )
    (net (code "96") (name "Net-(U1B-COUT)") (class "Default")
      (node (ref "R99") (pin "1") (pinfunction "1_1") (pintype "passive"))
      (node (ref "U1") (pin "G2") (pinfunction "COUT_G2") (pintype "passive"))
    )
    (net (code "97") (name "Net-(U1B-DIN)") (class "Default")
      (node (ref "R41") (pin "1") (pinfunction "1_1") (pintype "passive"))
      (node (ref "U1") (pin "E2") (pinfunction "DIN_E2") (pintype "passive"))
    )
    (net (code "98") (name "Net-(U1B-DOUT)") (class "Default")
      (node (ref "R42") (pin "1") (pinfunction "1_1") (pintype "passive"))
      (node (ref "U1") (pin "F1") (pinfunction "DOUT_F1") (pintype "passive"))
    )
    (net (code "99") (name "Net-(U1C-SPI_CLKOUT)") (class "Default")
      (node (ref "R74") (pin "1") (pinfunction "1_1") (pintype "passive"))
      (node (ref "U1") (pin "K1") (pinfunction "SPI_CLKOUT_K1") (pintype "passive"))
    )
    (net (code "100") (name "Net-(U1C-SPI_FSSOUT)") (class "Default")
      (node (ref "R75") (pin "1") (pinfunction "1_1") (pintype "passive"))
      (node (ref "U1") (pin "J2") (pinfunction "SPI_FSSOUT_J2") (pintype "passive"))
    )
    (net (code "101") (name "Net-(U1C-SPI_RXD)") (class "Default")
      (node (ref "R76") (pin "1") (pinfunction "1_1") (pintype "passive"))
      (node (ref "U1") (pin "J1") (pinfunction "SPI_RXD_J1") (pintype "passive"))
    )
    (net (code "102") (name "Net-(U1C-SPI_TXD)") (class "Default")
      (node (ref "R73") (pin "1") (pinfunction "1_1") (pintype "passive"))
      (node (ref "U1") (pin "J3") (pinfunction "SPI_TXD_J3") (pintype "passive"))
    )
    (net (code "103") (name "Net-(U1D-GPIO_0)") (class "Default")
      (node (ref "R17") (pin "1") (pinfunction "1_1") (pintype "passive"))
      (node (ref "U1") (pin "B2") (pinfunction "GPIO_0_B2") (pintype "passive"))
    )
    (net (code "104") (name "Net-(U1D-GPIO_1)") (class "Default")
      (node (ref "R18") (pin "1") (pinfunction "1_1") (pintype "passive"))
      (node (ref "U1") (pin "K2") (pinfunction "GPIO_1_K2") (pintype "passive"))
    )
    (net (code "105") (name "Net-(U1D-GPIO_2)") (class "Default")
      (node (ref "R19") (pin "1") (pinfunction "1_1") (pintype "passive"))
      (node (ref "U1") (pin "A2") (pinfunction "GPIO_2_A2") (pintype "passive"))
    )
    (net (code "106") (name "Net-(U1D-GPIO_3)") (class "Default")
      (node (ref "R20") (pin "1") (pinfunction "1_1") (pintype "passive"))
      (node (ref "U1") (pin "K3") (pinfunction "GPIO_3_K3") (pintype "passive"))
    )
    (net (code "107") (name "Net-(U1D-GPIO_4)") (class "Default")
      (node (ref "R21") (pin "1") (pinfunction "1_1") (pintype "passive"))
      (node (ref "U1") (pin "B3") (pinfunction "GPIO_4_B3") (pintype "passive"))
    )
    (net (code "108") (name "Net-(U1D-GPIO_5)") (class "Default")
      (node (ref "R22") (pin "1") (pinfunction "1_1") (pintype "passive"))
      (node (ref "U1") (pin "J4") (pinfunction "GPIO_5_J4") (pintype "passive"))
    )
    (net (code "109") (name "Net-(U1D-GPIO_6)") (class "Default")
      (node (ref "R23") (pin "1") (pinfunction "1_1") (pintype "passive"))
      (node (ref "U1") (pin "A3") (pinfunction "GPIO_6_A3") (pintype "passive"))
    )
    (net (code "110") (name "Net-(U1D-GPIO_7)") (class "Default")
      (node (ref "R24") (pin "1") (pinfunction "1_1") (pintype "passive"))
      (node (ref "U1") (pin "K4") (pinfunction "GPIO_7_K4") (pintype "passive"))
    )
    (net (code "111") (name "Net-(U1D-GPIO_8)") (class "Default")
      (node (ref "R25") (pin "1") (pinfunction "1_1") (pintype "passive"))
      (node (ref "U1") (pin "B4") (pinfunction "GPIO_8_B4") (pintype "passive"))
    )
    (net (code "112") (name "Net-(U1D-GPIO_9)") (class "Default")
      (node (ref "R26") (pin "1") (pinfunction "1_1") (pintype "passive"))
      (node (ref "U1") (pin "K5") (pinfunction "GPIO_9_K5") (pintype "passive"))
    )
    (net (code "113") (name "Net-(U1D-GPIO_10)") (class "Default")
      (node (ref "R27") (pin "1") (pinfunction "1_1") (pintype "passive"))
      (node (ref "U1") (pin "A4") (pinfunction "GPIO_10_A4") (pintype "passive"))
    )
    (net (code "114") (name "Net-(U1D-GPIO_11)") (class "Default")
      (node (ref "R28") (pin "1") (pinfunction "1_1") (pintype "passive"))
      (node (ref "U1") (pin "J5") (pinfunction "GPIO_11_J5") (pintype "passive"))
    )
    (net (code "115") (name "Net-(U1D-GPIO_12)") (class "Default")
      (node (ref "R29") (pin "1") (pinfunction "1_1") (pintype "passive"))
      (node (ref "U1") (pin "B5") (pinfunction "GPIO_12_B5") (pintype "passive"))
    )
    (net (code "116") (name "Net-(U1D-GPIO_13)") (class "Default")
      (node (ref "R30") (pin "1") (pinfunction "1_1") (pintype "passive"))
      (node (ref "U1") (pin "K6") (pinfunction "GPIO_13_K6") (pintype "passive"))
    )
    (net (code "117") (name "Net-(U1D-GPIO_14)") (class "Default")
      (node (ref "R31") (pin "1") (pinfunction "1_1") (pintype "passive"))
      (node (ref "U1") (pin "A5") (pinfunction "GPIO_14_A5") (pintype "passive"))
    )
    (net (code "118") (name "Net-(U1D-GPIO_15)") (class "Default")
      (node (ref "R32") (pin "1") (pinfunction "1_1") (pintype "passive"))
      (node (ref "U1") (pin "J6") (pinfunction "GPIO_15_J6") (pintype "passive"))
    )
    (net (code "119") (name "Net-(U1D-GPIO_16)") (class "Default")
      (node (ref "R33") (pin "1") (pinfunction "1_1") (pintype "passive"))
      (node (ref "U1") (pin "B6") (pinfunction "GPIO_16_B6") (pintype "passive"))
    )
    (net (code "120") (name "Net-(U1D-GPIO_17)") (class "Default")
      (node (ref "R34") (pin "1") (pinfunction "1_1") (pintype "passive"))
      (node (ref "U1") (pin "K7") (pinfunction "GPIO_17_K7") (pintype "passive"))
    )
    (net (code "121") (name "Net-(U1D-GPIO_18)") (class "Default")
      (node (ref "R35") (pin "1") (pinfunction "1_1") (pintype "passive"))
      (node (ref "U1") (pin "A6") (pinfunction "GPIO_18_A6") (pintype "passive"))
    )
    (net (code "122") (name "Net-(U1D-GPIO_19)") (class "Default")
      (node (ref "R36") (pin "1") (pinfunction "1_1") (pintype "passive"))
      (node (ref "U1") (pin "J7") (pinfunction "GPIO_19_J7") (pintype "passive"))
    )
    (net (code "123") (name "Net-(U1D-GPIO_20)") (class "Default")
      (node (ref "R37") (pin "1") (pinfunction "1_1") (pintype "passive"))
      (node (ref "U1") (pin "A7") (pinfunction "GPIO_20_A7") (pintype "passive"))
    )
    (net (code "124") (name "Net-(U1D-GPIO_21)") (class "Default")
      (node (ref "R38") (pin "1") (pinfunction "1_1") (pintype "passive"))
      (node (ref "U1") (pin "K8") (pinfunction "GPIO_21_K8") (pintype "passive"))
    )
    (net (code "125") (name "Net-(U1D-GPIO_22)") (class "Default")
      (node (ref "R39") (pin "1") (pinfunction "1_1") (pintype "passive"))
      (node (ref "U1") (pin "B7") (pinfunction "GPIO_22_B7") (pintype "passive"))
    )
    (net (code "126") (name "Net-(U1D-GPIO_23)") (class "Default")
      (node (ref "R40") (pin "1") (pinfunction "1_1") (pintype "passive"))
      (node (ref "U1") (pin "J8") (pinfunction "GPIO_23_J8") (pintype "passive"))
    )
    (net (code "127") (name "Net-(U1E-ECI)") (class "Default")
      (node (ref "R101") (pin "1") (pinfunction "1_1") (pintype "passive"))
      (node (ref "U1") (pin "H1") (pinfunction "ECI_H1") (pintype "passive"))
    )
    (net (code "128") (name "Net-(U1E-EDI)") (class "Default")
      (node (ref "R102") (pin "1") (pinfunction "1_1") (pintype "passive"))
      (node (ref "U1") (pin "H2") (pinfunction "EDI_H2") (pintype "passive"))
    )
    (net (code "129") (name "Net-(U1E-EMO)") (class "Default")
      (node (ref "R100") (pin "1") (pinfunction "1_1") (pintype "passive"))
      (node (ref "U1") (pin "B1") (pinfunction "EMO_B1") (pintype "passive"))
    )
    (net (code "130") (name "VCC_1P2") (class "Default")
      (node (ref "C54") (pin "2") (pinfunction "2_2") (pintype "passive"))
      (node (ref "U5") (pin "8") (pinfunction "VCC_8") (pintype "passive"))
    )
    (net (code "131") (name "VCC_M3_0P6") (class "Default")
      (node (ref "P2") (pin "3") (pinfunction "3_3") (pintype "passive"))
    )
    (net (code "132") (name "VCC_M3_1P2") (class "Default")
      (node (ref "C31") (pin "2") (pinfunction "2_2") (pintype "passive"))
      (node (ref "C55") (pin "2") (pinfunction "2_2") (pintype "passive"))
      (node (ref "P2") (pin "5") (pinfunction "5_5") (pintype "passive"))
      (node (ref "U2") (pin "8") (pinfunction "VCC_8") (pintype "passive"))
      (node (ref "U6") (pin "8") (pinfunction "VCC_8") (pintype "passive"))
    )
    (net (code "133") (name "VCC_M3_VBATT") (class "Default")
      (node (ref "P2") (pin "7") (pinfunction "7_7") (pintype "passive"))
    )
    (net (code "134") (name "VCC_SOL") (class "Default")
      (node (ref "P2") (pin "1") (pinfunction "1_1") (pintype "passive"))
    )
    (net (code "135") (name "unconnected-(R97-Pad2)") (class "Default")
      (node (ref "R97") (pin "2") (pinfunction "2_2") (pintype "passive"))
    )
    (net (code "136") (name "unconnected-(U2-3Y-Pad2)") (class "Default")
      (node (ref "U2") (pin "2") (pinfunction "3Y_2") (pintype "passive"))
    )
    (net (code "137") (name "unconnected-(U5-3Y-Pad2)") (class "Default")
      (node (ref "U5") (pin "2") (pinfunction "3Y_2") (pintype "passive"))
    )
  )
)
